# Handmouse_Sch.net
KiCad netlist of a schematic drawn in Altium Designer
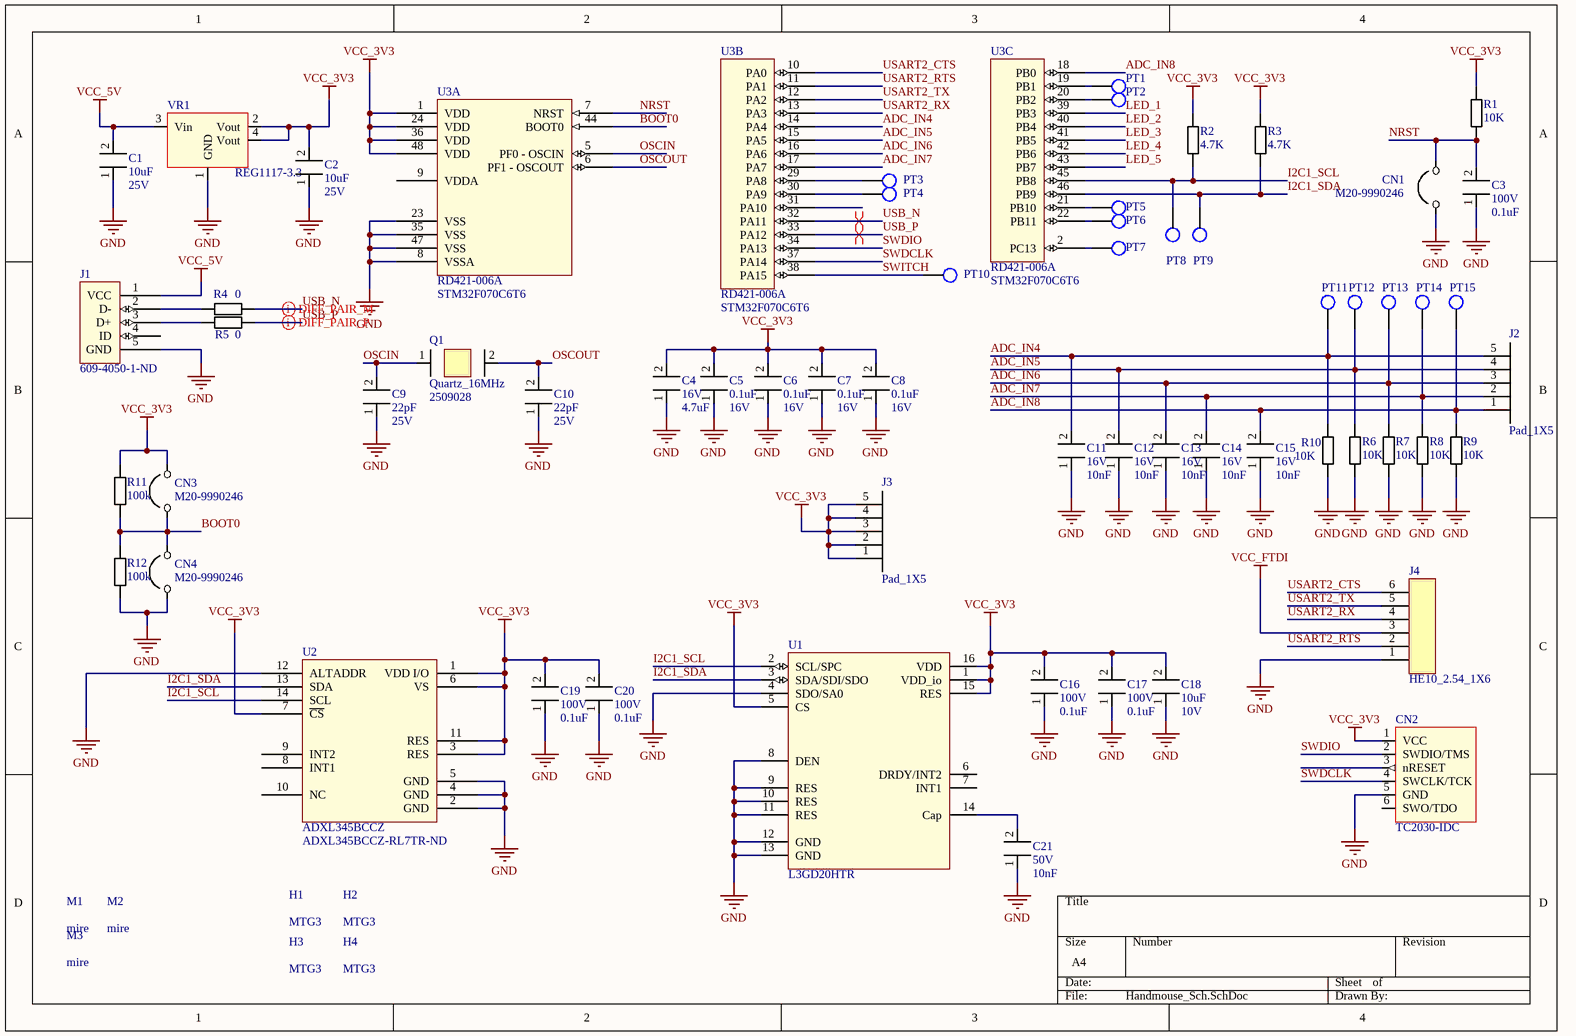
[diagram p0: Handmouse_Sch.SchDoc]

(export (version "E")
  (design (tool "Eeschema 10.0.6"))
  (components
    (comp (ref "C1")
      (value "RD401-040A")
      (footprint "1206")
      (description "CAP CER 1206 10uF 25V X7R 10%")
      (fields
        (field (name "MANUFACTURER") "MURATA")
        (field (name "MANUFACTURER PART NUMBER") "GRM31CR71E106KA12L")
        (field (name "CAPACITÉ") "10uF")
        (field (name "TENSION") "25V")
      )
      (libsource (lib "Condensateur") (part "RD401-040A"))
    )
    (comp (ref "C2")
      (value "RD401-040A")
      (footprint "1206")
      (description "CAP CER 1206 10uF 25V X7R 10%")
      (fields
        (field (name "MANUFACTURER") "MURATA")
        (field (name "MANUFACTURER PART NUMBER") "GRM31CR71E106KA12L")
        (field (name "CAPACITÉ") "10uF")
        (field (name "TENSION") "25V")
      )
      (libsource (lib "Condensateur") (part "RD401-040A"))
    )
    (comp (ref "C3")
      (value "RD401-002A")
      (footprint "0805")
      (description "CAP CER 0805 0.1uF 100V X7R 5%")
      (fields
        (field (name "TENSION") "100V")
        (field (name "CAPACITÉ") "0.1uF")
        (field (name "HAUTEUR DU BOÎTIER") "1.4 mm")
      )
      (libsource (lib "Condensateur") (part "RD401-002A"))
    )
    (comp (ref "C4")
      (value "~")
      (footprint "0805")
      (description "CAP CER 0805 4.7uF 16V X7R 10%")
      (fields
        (field (name "MANUFACTURER") "AVX")
        (field (name "MANUFACTURER PART NUMBER") "0805YC475KAT2A")
        (field (name "VOLTAGE") "16V")
        (field (name "CAPACITÉ") "4.7uF")
      )
      (libsource (lib "Condensateur") (part "RD401-025A"))
    )
    (comp (ref "C5")
      (value "RD401-033A")
      (footprint "0402")
      (description "CAP CER 0402 0.1uF 16V X7R 5%")
      (fields
        (field (name "MANUFACTURER") "KEMET")
        (field (name "MANUFACTURER PART NUMBER") "C0402C104J4RACTU")
        (field (name "CAPACITÉ") "0.1uF")
        (field (name "VOLTAGE") "16V")
      )
      (libsource (lib "Condensateur") (part "RD401-033A"))
    )
    (comp (ref "C6")
      (value "RD401-033A")
      (footprint "0402")
      (description "CAP CER 0402 0.1uF 16V X7R 5%")
      (fields
        (field (name "MANUFACTURER") "KEMET")
        (field (name "MANUFACTURER PART NUMBER") "C0402C104J4RACTU")
        (field (name "CAPACITÉ") "0.1uF")
        (field (name "VOLTAGE") "16V")
      )
      (libsource (lib "Condensateur") (part "RD401-033A"))
    )
    (comp (ref "C7")
      (value "RD401-033A")
      (footprint "0402")
      (description "CAP CER 0402 0.1uF 16V X7R 5%")
      (fields
        (field (name "MANUFACTURER") "KEMET")
        (field (name "MANUFACTURER PART NUMBER") "C0402C104J4RACTU")
        (field (name "CAPACITÉ") "0.1uF")
        (field (name "VOLTAGE") "16V")
      )
      (libsource (lib "Condensateur") (part "RD401-033A"))
    )
    (comp (ref "C8")
      (value "RD401-033A")
      (footprint "0402")
      (description "CAP CER 0402 0.1uF 16V X7R 5%")
      (fields
        (field (name "MANUFACTURER") "KEMET")
        (field (name "MANUFACTURER PART NUMBER") "C0402C104J4RACTU")
        (field (name "CAPACITÉ") "0.1uF")
        (field (name "VOLTAGE") "16V")
      )
      (libsource (lib "Condensateur") (part "RD401-033A"))
    )
    (comp (ref "C9")
      (value "22pF")
      (footprint "0402")
      (description "CAP CER 0402 22pF 25V COG 1%")
      (fields (field (name "VOLTAGE") "25V"))
      (libsource (lib "Condensateur") (part "RD401-009A"))
    )
    (comp (ref "C10")
      (value "22pF")
      (footprint "0402")
      (description "CAP CER 0402 22pF 25V COG 1%")
      (fields (field (name "VOLTAGE") "25V"))
      (libsource (lib "Condensateur") (part "RD401-009A"))
    )
    (comp (ref "C11")
      (value "RD401-008A")
      (footprint "0402")
      (description "CAP CER 0402 10nF 16V X7R 5%")
      (fields (field (name "VOLTAGE") "16V") (field (name "CAPACITÉ") "10nF"))
      (libsource (lib "Condensateur") (part "RD401-008A"))
    )
    (comp (ref "C12")
      (value "RD401-008A")
      (footprint "0402")
      (description "CAP CER 0402 10nF 16V X7R 5%")
      (fields (field (name "VOLTAGE") "16V") (field (name "CAPACITÉ") "10nF"))
      (libsource (lib "Condensateur") (part "RD401-008A"))
    )
    (comp (ref "C13")
      (value "RD401-008A")
      (footprint "0402")
      (description "CAP CER 0402 10nF 16V X7R 5%")
      (fields (field (name "VOLTAGE") "16V") (field (name "CAPACITÉ") "10nF"))
      (libsource (lib "Condensateur") (part "RD401-008A"))
    )
    (comp (ref "C14")
      (value "RD401-008A")
      (footprint "0402")
      (description "CAP CER 0402 10nF 16V X7R 5%")
      (fields (field (name "VOLTAGE") "16V") (field (name "CAPACITÉ") "10nF"))
      (libsource (lib "Condensateur") (part "RD401-008A"))
    )
    (comp (ref "C15")
      (value "RD401-008A")
      (footprint "0402")
      (description "CAP CER 0402 10nF 16V X7R 5%")
      (fields (field (name "VOLTAGE") "16V") (field (name "CAPACITÉ") "10nF"))
      (libsource (lib "Condensateur") (part "RD401-008A"))
    )
    (comp (ref "C16")
      (value "RD401-002A")
      (footprint "0805")
      (description "CAP CER 0805 0.1uF 100V X7R 5%")
      (fields
        (field (name "TENSION") "100V")
        (field (name "CAPACITÉ") "0.1uF")
        (field (name "HAUTEUR DU BOÎTIER") "1.4 mm")
      )
      (libsource (lib "Condensateur") (part "RD401-002A"))
    )
    (comp (ref "C17")
      (value "RD401-002A")
      (footprint "0805")
      (description "CAP CER 0805 0.1uF 100V X7R 5%")
      (fields
        (field (name "TENSION") "100V")
        (field (name "CAPACITÉ") "0.1uF")
        (field (name "HAUTEUR DU BOÎTIER") "1.4 mm")
      )
      (libsource (lib "Condensateur") (part "RD401-002A"))
    )
    (comp (ref "C18")
      (value "RD401-042A")
      (footprint "0805")
      (description "CAP CER 0805 10uF 10V X7R 10%")
      (fields
        (field (name "MANUFACTURER") "MURATA")
        (field (name "MANUFACTURER PART NUMBER") "GRM21BR71A106KE51L")
        (field (name "CAPACITÉ") "10uF")
        (field (name "TENSION") "10V")
      )
      (libsource (lib "Condensateur") (part "RD401-042A"))
    )
    (comp (ref "C19")
      (value "RD401-002A")
      (footprint "0805")
      (description "CAP CER 0805 0.1uF 100V X7R 5%")
      (fields
        (field (name "TENSION") "100V")
        (field (name "CAPACITÉ") "0.1uF")
        (field (name "HAUTEUR DU BOÎTIER") "1.4 mm")
      )
      (libsource (lib "Condensateur") (part "RD401-002A"))
    )
    (comp (ref "C20")
      (value "RD401-002A")
      (footprint "0805")
      (description "CAP CER 0805 0.1uF 100V X7R 5%")
      (fields
        (field (name "TENSION") "100V")
        (field (name "CAPACITÉ") "0.1uF")
        (field (name "HAUTEUR DU BOÎTIER") "1.4 mm")
      )
      (libsource (lib "Condensateur") (part "RD401-002A"))
    )
    (comp (ref "C21")
      (value "RD401-037A")
      (footprint "0402")
      (description "CAP CER 0402 10nF 50V X7R 10%")
      (fields
        (field (name "MANUFACTURER") "KEMET")
        (field (name "MANUFACTURER PART NUMBER") "C0402C103K5RACTU")
        (field (name "VOLTAGE") "50V")
        (field (name "CAPACITE") "10nF")
      )
      (libsource (lib "Condensateur") (part "RD401-037A"))
    )
    (comp (ref "CN1")
      (value "RD408-013A")
      (footprint "PinHead 2*1 M")
      (description "JUMPER")
      (fields (field (name "MANUFACTURER PART NUMBER 1") "M20-9990246"))
      (libsource (lib "Connecteur") (part "RD408-013A"))
    )
    (comp (ref "CN2")
      (value "RD408-022A")
      (footprint "TC2030-IDC-FP")
      (description "CON SWD")
      (fields
        (field (name "MANUFACTURER") "Tag-Connect LLC")
        (field (name "MANUFACTURER PART NUMBER") "TC2030-IDC")
      )
      (libsource (lib "Connecteur") (part "RD408-022A"))
    )
    (comp (ref "CN3")
      (value "RD408-013A")
      (footprint "PinHead 2*1 M")
      (description "JUMPER")
      (fields (field (name "MANUFACTURER PART NUMBER 1") "M20-9990246"))
      (libsource (lib "Connecteur") (part "RD408-013A"))
    )
    (comp (ref "CN4")
      (value "RD408-013A")
      (footprint "PinHead 2*1 M")
      (description "JUMPER")
      (fields (field (name "MANUFACTURER PART NUMBER 1") "M20-9990246"))
      (libsource (lib "Connecteur") (part "RD408-013A"))
    )
    (comp (ref "H1")
      (value "MTG3")
      (footprint "MTG3")
      (description "Mounting hole M3")
      (libsource (lib "Miscellaneous") (part "MTG3"))
    )
    (comp (ref "H2")
      (value "MTG3")
      (footprint "MTG3")
      (description "Mounting hole M3")
      (libsource (lib "Miscellaneous") (part "MTG3"))
    )
    (comp (ref "H3")
      (value "MTG3")
      (footprint "MTG3")
      (description "Mounting hole M3")
      (libsource (lib "Miscellaneous") (part "MTG3"))
    )
    (comp (ref "H4")
      (value "MTG3")
      (footprint "MTG3")
      (description "Mounting hole M3")
      (libsource (lib "Miscellaneous") (part "MTG3"))
    )
    (comp (ref "J1")
      (value "CONN_FCI_10103594-0001LF")
      (description "CONN MICROUSB FCI 10103594-0001LF")
      (fields
        (field (name "MANUFACTURER") "Amphenol FCI")
        (field (name "MANUFACTURER PART NUMBER") "10103594-0001LF")
        (field (name "SUPPLIER PART NUMBER 1") "609-4050-1-ND")
      )
      (libsource (lib "Schlib1") (part "CONN_FCI_10103594-0001LF"))
    )
    (comp (ref "J2") (value "Pad_1X5") (libsource (lib "Schlib1") (part "Pad_1X5")))
    (comp (ref "J3") (value "Pad_1X5") (libsource (lib "Schlib1") (part "Pad_1X5")))
    (comp (ref "J4") (value "HE10_2.54_1X6") (libsource (lib "Schlib1") (part "HE10_2.54_1X6")))
    (comp (ref "M1")
      (value "mire")
      (footprint "Miscellaneous:Mire")
      (libsource (lib "Miscellaneous") (part "mire"))
    )
    (comp (ref "M2")
      (value "mire")
      (footprint "Miscellaneous:Mire")
      (libsource (lib "Miscellaneous") (part "mire"))
    )
    (comp (ref "M3")
      (value "mire")
      (footprint "Miscellaneous:Mire")
      (libsource (lib "Miscellaneous") (part "mire"))
    )
    (comp (ref "PT1")
      (value "PT 0.8mm")
      (description "Point de test pastille 0.8mm")
      (libsource (lib "Schlib1") (part "PT 0.8mm"))
    )
    (comp (ref "PT2")
      (value "PT 0.8mm")
      (description "Point de test pastille 0.8mm")
      (libsource (lib "Schlib1") (part "PT 0.8mm"))
    )
    (comp (ref "PT3")
      (value "PT 0.8mm")
      (description "Point de test pastille 0.8mm")
      (libsource (lib "Schlib1") (part "PT 0.8mm"))
    )
    (comp (ref "PT4")
      (value "PT 0.8mm")
      (description "Point de test pastille 0.8mm")
      (libsource (lib "Schlib1") (part "PT 0.8mm"))
    )
    (comp (ref "PT5")
      (value "PT 0.8mm")
      (description "Point de test pastille 0.8mm")
      (libsource (lib "Schlib1") (part "PT 0.8mm"))
    )
    (comp (ref "PT6")
      (value "PT 0.8mm")
      (description "Point de test pastille 0.8mm")
      (libsource (lib "Schlib1") (part "PT 0.8mm"))
    )
    (comp (ref "PT7")
      (value "PT 0.8mm")
      (description "Point de test pastille 0.8mm")
      (libsource (lib "Schlib1") (part "PT 0.8mm"))
    )
    (comp (ref "PT8")
      (value "PT 0.8mm")
      (description "Point de test pastille 0.8mm")
      (libsource (lib "Schlib1") (part "PT 0.8mm"))
    )
    (comp (ref "PT9")
      (value "PT 0.8mm")
      (description "Point de test pastille 0.8mm")
      (libsource (lib "Schlib1") (part "PT 0.8mm"))
    )
    (comp (ref "PT10")
      (value "PT 0.8mm")
      (description "Point de test pastille 0.8mm")
      (libsource (lib "Schlib1") (part "PT 0.8mm"))
    )
    (comp (ref "PT11")
      (value "PT 0.8mm")
      (description "Point de test pastille 0.8mm")
      (libsource (lib "Schlib1") (part "PT 0.8mm"))
    )
    (comp (ref "PT12")
      (value "PT 0.8mm")
      (description "Point de test pastille 0.8mm")
      (libsource (lib "Schlib1") (part "PT 0.8mm"))
    )
    (comp (ref "PT13")
      (value "PT 0.8mm")
      (description "Point de test pastille 0.8mm")
      (libsource (lib "Schlib1") (part "PT 0.8mm"))
    )
    (comp (ref "PT14")
      (value "PT 0.8mm")
      (description "Point de test pastille 0.8mm")
      (libsource (lib "Schlib1") (part "PT 0.8mm"))
    )
    (comp (ref "PT15")
      (value "PT 0.8mm")
      (description "Point de test pastille 0.8mm")
      (libsource (lib "Schlib1") (part "PT 0.8mm"))
    )
    (comp (ref "Q1")
      (value "Quartz_16MHz")
      (description "Quartz 16MHz")
      (fields
        (field (name "MANUFACTURER") "RALTRON")
        (field (name "MANUFACTURER PART NUMBER") "AS-16.000-18-SMD")
        (field (name "SUPPLIER PART NUMBER 1") "2509028")
      )
      (libsource (lib "Schlib1") (part "Quartz_16MHz"))
    )
    (comp (ref "R1")
      (value "RD403-054A")
      (footprint "0603")
      (description "RES 0603 10K 1% 0.1W")
      (fields
        (field (name "MANUFACTURER") "VISHAY DRALORIC")
        (field (name "MANUFACTURER PART NUMBER") "CRCW060310K0FKEA")
        (field (name "RESISTANCE") "10K")
      )
      (libsource (lib "Resistance") (part "RD403-054A"))
    )
    (comp (ref "R2")
      (value "RD403-046A")
      (footprint "0603")
      (description "RES 0603 4.7K 1% 0.1W")
      (fields
        (field (name "MANUFACTURER") "Vishay Dale")
        (field (name "MANUFACTURER PART NUMBER") "CRCW06034K70FKEA")
        (field (name "RÉSISTANCE (OHMS)") "4.7K")
        (field (name "HAUTEUR") "0,020 po (0,50 mm)")
      )
      (libsource (lib "Resistance") (part "RD403-046A"))
    )
    (comp (ref "R3")
      (value "RD403-046A")
      (footprint "0603")
      (description "RES 0603 4.7K 1% 0.1W")
      (fields
        (field (name "MANUFACTURER") "Vishay Dale")
        (field (name "MANUFACTURER PART NUMBER") "CRCW06034K70FKEA")
        (field (name "RÉSISTANCE (OHMS)") "4.7K")
        (field (name "HAUTEUR") "0,020 po (0,50 mm)")
      )
      (libsource (lib "Resistance") (part "RD403-046A"))
    )
    (comp (ref "R4")
      (value "RD403-044A")
      (footprint "0603")
      (description "RES 0603 0 1% 0.1W")
      (fields
        (field (name "MANUFACTURER") "VISHAY DRALORIC")
        (field (name "MANUFACTURER PART NUMBER") "CRCW06030000Z0EA")
        (field (name "RÉSISTANCE") "0")
      )
      (libsource (lib "Resistance") (part "RD403-044A"))
    )
    (comp (ref "R5")
      (value "RD403-044A")
      (footprint "0603")
      (description "RES 0603 0 1% 0.1W")
      (fields
        (field (name "MANUFACTURER") "VISHAY DRALORIC")
        (field (name "MANUFACTURER PART NUMBER") "CRCW06030000Z0EA")
        (field (name "RÉSISTANCE") "0")
      )
      (libsource (lib "Resistance") (part "RD403-044A"))
    )
    (comp (ref "R6")
      (value "RD403-054A")
      (footprint "0603")
      (description "RES 0603 10K 1% 0.1W")
      (fields
        (field (name "MANUFACTURER") "VISHAY DRALORIC")
        (field (name "MANUFACTURER PART NUMBER") "CRCW060310K0FKEA")
        (field (name "RESISTANCE") "10K")
      )
      (libsource (lib "Resistance") (part "RD403-054A"))
    )
    (comp (ref "R7")
      (value "RD403-054A")
      (footprint "0603")
      (description "RES 0603 10K 1% 0.1W")
      (fields
        (field (name "MANUFACTURER") "VISHAY DRALORIC")
        (field (name "MANUFACTURER PART NUMBER") "CRCW060310K0FKEA")
        (field (name "RESISTANCE") "10K")
      )
      (libsource (lib "Resistance") (part "RD403-054A"))
    )
    (comp (ref "R8")
      (value "RD403-054A")
      (footprint "0603")
      (description "RES 0603 10K 1% 0.1W")
      (fields
        (field (name "MANUFACTURER") "VISHAY DRALORIC")
        (field (name "MANUFACTURER PART NUMBER") "CRCW060310K0FKEA")
        (field (name "RESISTANCE") "10K")
      )
      (libsource (lib "Resistance") (part "RD403-054A"))
    )
    (comp (ref "R9")
      (value "RD403-054A")
      (footprint "0603")
      (description "RES 0603 10K 1% 0.1W")
      (fields
        (field (name "MANUFACTURER") "VISHAY DRALORIC")
        (field (name "MANUFACTURER PART NUMBER") "CRCW060310K0FKEA")
        (field (name "RESISTANCE") "10K")
      )
      (libsource (lib "Resistance") (part "RD403-054A"))
    )
    (comp (ref "R10")
      (value "RD403-054A")
      (footprint "0603")
      (description "RES 0603 10K 1% 0.1W")
      (fields
        (field (name "MANUFACTURER") "VISHAY DRALORIC")
        (field (name "MANUFACTURER PART NUMBER") "CRCW060310K0FKEA")
        (field (name "RESISTANCE") "10K")
      )
      (libsource (lib "Resistance") (part "RD403-054A"))
    )
    (comp (ref "R11")
      (value "100k")
      (footprint "0402")
      (description "RES 0402 100k 1% 0.063W")
      (libsource (lib "Resistance") (part "RD403-007A"))
    )
    (comp (ref "R12")
      (value "100k")
      (footprint "0402")
      (description "RES 0402 100k 1% 0.063W")
      (libsource (lib "Resistance") (part "RD403-007A"))
    )
    (comp (ref "U1")
      (value "RD498-005A")
      (footprint "LGA_50P_300X300_16")
      (description "Gyroscopes MEMS motion sensor 3axis digital output")
      (fields (field (name "MANUFACTURER PART NUMBER 1") "L3GD20HTR") (field (name "HAUTEUR") "1 mm"))
      (libsource (lib "Miscellaneous") (part "RD498-005A"))
    )
    (comp (ref "U2")
      (value "ADXL345BCCZ")
      (fields
        (field (name "MANUFACTURER") "Analog Devices Inc.")
        (field (name "MANUFACTURER PART NUMBER") "ADXL345BCCZ-RL7")
        (field (name "SUPPLIER PART NUMBER 1") "ADXL345BCCZ-RL7TR-ND")
      )
      (libsource (lib "Schlib1") (part "ADXL345BCCZ"))
    )
    (comp (ref "U3")
      (value "RD421-006A")
      (description "STM32F070C6T6")
      (fields
        (field (name "MANUFACTURER") "STMICROELECTRONICS")
        (field (name "MANUFACTURER PART NUMBER") "STM32F070C6T6")
      )
      (libsource (lib "SOC") (part "RD421-006A"))
    )
    (comp (ref "VR1")
      (value "RD426-001A")
      (footprint "R-PDSO- G4")
      (description "REG LIN SOT223 3V3 1A 3.8V 15V")
      (fields (field (name "MANUFACTURER PART NUMBER 1") "REG1117-3.3"))
      (libsource (lib "Lineaire") (part "RD426-001A"))
    )
  )
  (nets
    (net (code "1") (name "/ADC_IN4") (class "Default")
      (node (ref "C11") (pin "2") (pinfunction "2_2") (pintype "passive"))
      (node (ref "J2") (pin "5") (pinfunction "5_5") (pintype "passive"))
      (node (ref "PT11") (pin "1") (pinfunction "1_1") (pintype "passive"))
      (node (ref "R10") (pin "2") (pinfunction "4_2") (pintype "passive"))
      (node (ref "U3") (pin "14") (pinfunction "PA4_14") (pintype "bidirectional"))
    )
    (net (code "2") (name "/ADC_IN5") (class "Default")
      (node (ref "C12") (pin "2") (pinfunction "2_2") (pintype "passive"))
      (node (ref "J2") (pin "4") (pinfunction "4_4") (pintype "passive"))
      (node (ref "PT12") (pin "1") (pinfunction "1_1") (pintype "passive"))
      (node (ref "R6") (pin "2") (pinfunction "4_2") (pintype "passive"))
      (node (ref "U3") (pin "15") (pinfunction "PA5_15") (pintype "bidirectional"))
    )
    (net (code "3") (name "/ADC_IN6") (class "Default")
      (node (ref "C13") (pin "2") (pinfunction "2_2") (pintype "passive"))
      (node (ref "J2") (pin "3") (pinfunction "3_3") (pintype "passive"))
      (node (ref "PT13") (pin "1") (pinfunction "1_1") (pintype "passive"))
      (node (ref "R7") (pin "2") (pinfunction "4_2") (pintype "passive"))
      (node (ref "U3") (pin "16") (pinfunction "PA6_16") (pintype "bidirectional"))
    )
    (net (code "4") (name "/ADC_IN7") (class "Default")
      (node (ref "C14") (pin "2") (pinfunction "2_2") (pintype "passive"))
      (node (ref "J2") (pin "2") (pinfunction "2_2") (pintype "passive"))
      (node (ref "PT14") (pin "1") (pinfunction "1_1") (pintype "passive"))
      (node (ref "R8") (pin "2") (pinfunction "4_2") (pintype "passive"))
      (node (ref "U3") (pin "17") (pinfunction "PA7_17") (pintype "bidirectional"))
    )
    (net (code "5") (name "/ADC_IN8") (class "Default")
      (node (ref "C15") (pin "2") (pinfunction "2_2") (pintype "passive"))
      (node (ref "J2") (pin "1") (pinfunction "1_1") (pintype "passive"))
      (node (ref "PT15") (pin "1") (pinfunction "1_1") (pintype "passive"))
      (node (ref "R9") (pin "2") (pinfunction "4_2") (pintype "passive"))
      (node (ref "U3") (pin "18") (pinfunction "PB0_18") (pintype "bidirectional"))
    )
    (net (code "6") (name "/BOOT0") (class "Default")
      (node (ref "CN3") (pin "1") (pinfunction "1_1") (pintype "power_in"))
      (node (ref "CN4") (pin "2") (pinfunction "2_2") (pintype "power_in"))
      (node (ref "R11") (pin "1") (pinfunction "3_1") (pintype "passive"))
      (node (ref "R12") (pin "2") (pinfunction "4_2") (pintype "passive"))
      (node (ref "U3") (pin "44") (pinfunction "BOOT0_44") (pintype "input"))
    )
    (net (code "7") (name "/I2C1_SCL") (class "Default")
      (node (ref "PT8") (pin "1") (pinfunction "1_1") (pintype "passive"))
      (node (ref "R2") (pin "1") (pinfunction "3_1") (pintype "passive"))
      (node (ref "U1") (pin "2") (pinfunction "SCL/SPC_2") (pintype "bidirectional"))
      (node (ref "U2") (pin "14") (pinfunction "SCL_14") (pintype "passive"))
      (node (ref "U3") (pin "45") (pinfunction "PB8_45") (pintype "bidirectional"))
    )
    (net (code "8") (name "/I2C1_SDA") (class "Default")
      (node (ref "PT9") (pin "1") (pinfunction "1_1") (pintype "passive"))
      (node (ref "R3") (pin "1") (pinfunction "3_1") (pintype "passive"))
      (node (ref "U1") (pin "3") (pinfunction "SDA/SDI/SDO_3") (pintype "bidirectional"))
      (node (ref "U2") (pin "13") (pinfunction "SDA_13") (pintype "passive"))
      (node (ref "U3") (pin "46") (pinfunction "PB9_46") (pintype "bidirectional"))
    )
    (net (code "9") (name "/LED_1") (class "Default")
      (node (ref "U3") (pin "39") (pinfunction "PB3_39") (pintype "bidirectional"))
    )
    (net (code "10") (name "/LED_2") (class "Default")
      (node (ref "U3") (pin "40") (pinfunction "PB4_40") (pintype "bidirectional"))
    )
    (net (code "11") (name "/LED_3") (class "Default")
      (node (ref "U3") (pin "41") (pinfunction "PB5_41") (pintype "bidirectional"))
    )
    (net (code "12") (name "/LED_4") (class "Default")
      (node (ref "U3") (pin "42") (pinfunction "PB6_42") (pintype "bidirectional"))
    )
    (net (code "13") (name "/LED_5") (class "Default")
      (node (ref "U3") (pin "43") (pinfunction "PB7_43") (pintype "bidirectional"))
    )
    (net (code "14") (name "/NRST") (class "Default")
      (node (ref "C3") (pin "2") (pinfunction "2_2") (pintype "passive"))
      (node (ref "CN1") (pin "2") (pinfunction "2_2") (pintype "power_in"))
      (node (ref "R1") (pin "1") (pinfunction "3_1") (pintype "passive"))
      (node (ref "U3") (pin "7") (pinfunction "NRST_7") (pintype "input"))
    )
    (net (code "15") (name "/OSCIN") (class "Default")
      (node (ref "C9") (pin "2") (pinfunction "2_2") (pintype "passive"))
      (node (ref "Q1") (pin "1") (pinfunction "1_1") (pintype "passive"))
      (node (ref "U3") (pin "5") (pinfunction "PF0_-_OSCIN_5") (pintype "bidirectional"))
    )
    (net (code "16") (name "/OSCOUT") (class "Default")
      (node (ref "C10") (pin "2") (pinfunction "2_2") (pintype "passive"))
      (node (ref "Q1") (pin "2") (pinfunction "2_2") (pintype "passive"))
      (node (ref "U3") (pin "6") (pinfunction "PF1_-_OSCOUT_6") (pintype "bidirectional"))
    )
    (net (code "17") (name "/SWDCLK") (class "Default")
      (node (ref "CN2") (pin "4") (pinfunction "SWCLK/TCK_4") (pintype "bidirectional"))
      (node (ref "U3") (pin "37") (pinfunction "PA14_37") (pintype "bidirectional"))
    )
    (net (code "18") (name "/SWDIO") (class "Default")
      (node (ref "CN2") (pin "2") (pinfunction "SWDIO/TMS_2") (pintype "bidirectional"))
      (node (ref "U3") (pin "34") (pinfunction "PA13_34") (pintype "bidirectional"))
    )
    (net (code "19") (name "/SWITCH") (class "Default")
      (node (ref "PT10") (pin "1") (pinfunction "1_1") (pintype "passive"))
      (node (ref "U3") (pin "38") (pinfunction "PA15_38") (pintype "bidirectional"))
    )
    (net (code "20") (name "/USART2_CTS") (class "Default")
      (node (ref "J4") (pin "6") (pinfunction "6_6") (pintype "passive"))
      (node (ref "U3") (pin "10") (pinfunction "PA0_10") (pintype "bidirectional"))
    )
    (net (code "21") (name "/USART2_RTS") (class "Default")
      (node (ref "J4") (pin "2") (pinfunction "2_2") (pintype "passive"))
      (node (ref "U3") (pin "11") (pinfunction "PA1_11") (pintype "bidirectional"))
    )
    (net (code "22") (name "/USART2_RX") (class "Default")
      (node (ref "J4") (pin "4") (pinfunction "4_4") (pintype "passive"))
      (node (ref "U3") (pin "13") (pinfunction "PA3_13") (pintype "bidirectional"))
    )
    (net (code "23") (name "/USART2_TX") (class "Default")
      (node (ref "J4") (pin "5") (pinfunction "5_5") (pintype "passive"))
      (node (ref "U3") (pin "12") (pinfunction "PA2_12") (pintype "bidirectional"))
    )
    (net (code "24") (name "/USB_N") (class "Default")
      (node (ref "R4") (pin "2") (pinfunction "4_2") (pintype "passive"))
      (node (ref "U3") (pin "32") (pinfunction "PA11_32") (pintype "bidirectional"))
    )
    (net (code "25") (name "/USB_P") (class "Default")
      (node (ref "R5") (pin "2") (pinfunction "4_2") (pintype "passive"))
      (node (ref "U3") (pin "33") (pinfunction "PA12_33") (pintype "bidirectional"))
    )
    (net (code "26") (name "GND") (class "Default")
      (node (ref "C1") (pin "1") (pinfunction "1_1") (pintype "passive"))
      (node (ref "C10") (pin "1") (pinfunction "1_1") (pintype "passive"))
      (node (ref "C11") (pin "1") (pinfunction "1_1") (pintype "passive"))
      (node (ref "C12") (pin "1") (pinfunction "1_1") (pintype "passive"))
      (node (ref "C13") (pin "1") (pinfunction "1_1") (pintype "passive"))
      (node (ref "C14") (pin "1") (pinfunction "1_1") (pintype "passive"))
      (node (ref "C15") (pin "1") (pinfunction "1_1") (pintype "passive"))
      (node (ref "C16") (pin "1") (pinfunction "1_1") (pintype "passive"))
      (node (ref "C17") (pin "1") (pinfunction "1_1") (pintype "passive"))
      (node (ref "C18") (pin "1") (pinfunction "1_1") (pintype "passive"))
      (node (ref "C19") (pin "1") (pinfunction "1_1") (pintype "passive"))
      (node (ref "C2") (pin "1") (pinfunction "1_1") (pintype "passive"))
      (node (ref "C20") (pin "1") (pinfunction "1_1") (pintype "passive"))
      (node (ref "C21") (pin "1") (pinfunction "1_1") (pintype "passive"))
      (node (ref "C3") (pin "1") (pinfunction "1_1") (pintype "passive"))
      (node (ref "C4") (pin "1") (pinfunction "1_1") (pintype "passive"))
      (node (ref "C5") (pin "1") (pinfunction "1_1") (pintype "passive"))
      (node (ref "C6") (pin "1") (pinfunction "1_1") (pintype "passive"))
      (node (ref "C7") (pin "1") (pinfunction "1_1") (pintype "passive"))
      (node (ref "C8") (pin "1") (pinfunction "1_1") (pintype "passive"))
      (node (ref "C9") (pin "1") (pinfunction "1_1") (pintype "passive"))
      (node (ref "CN1") (pin "1") (pinfunction "1_1") (pintype "power_in"))
      (node (ref "CN2") (pin "5") (pinfunction "GND_5") (pintype "power_in"))
      (node (ref "CN4") (pin "1") (pinfunction "1_1") (pintype "power_in"))
      (node (ref "J1") (pin "5") (pinfunction "GND_5") (pintype "power_in"))
      (node (ref "J4") (pin "1") (pinfunction "1_1") (pintype "passive"))
      (node (ref "R10") (pin "1") (pinfunction "3_1") (pintype "passive"))
      (node (ref "R12") (pin "1") (pinfunction "3_1") (pintype "passive"))
      (node (ref "R6") (pin "1") (pinfunction "3_1") (pintype "passive"))
      (node (ref "R7") (pin "1") (pinfunction "3_1") (pintype "passive"))
      (node (ref "R8") (pin "1") (pinfunction "3_1") (pintype "passive"))
      (node (ref "R9") (pin "1") (pinfunction "3_1") (pintype "passive"))
      (node (ref "U1") (pin "10") (pinfunction "RES_10") (pintype "passive"))
      (node (ref "U1") (pin "11") (pinfunction "RES_11") (pintype "passive"))
      (node (ref "U1") (pin "12") (pinfunction "GND_12") (pintype "power_in"))
      (node (ref "U1") (pin "13") (pinfunction "GND_13") (pintype "power_in"))
      (node (ref "U1") (pin "4") (pinfunction "SDO/SA0_4") (pintype "passive"))
      (node (ref "U1") (pin "8") (pinfunction "DEN_8") (pintype "passive"))
      (node (ref "U1") (pin "9") (pinfunction "RES_9") (pintype "passive"))
      (node (ref "U2") (pin "12") (pinfunction "ALTADDR_12") (pintype "passive"))
      (node (ref "U2") (pin "2") (pinfunction "GND_2") (pintype "power_in"))
      (node (ref "U2") (pin "4") (pinfunction "GND_4") (pintype "power_in"))
      (node (ref "U2") (pin "5") (pinfunction "GND_5") (pintype "power_in"))
      (node (ref "U3") (pin "23") (pinfunction "VSS_23") (pintype "power_in"))
      (node (ref "U3") (pin "35") (pinfunction "VSS_35") (pintype "power_in"))
      (node (ref "U3") (pin "47") (pinfunction "VSS_47") (pintype "power_in"))
      (node (ref "U3") (pin "8") (pinfunction "VSSA_8") (pintype "power_in"))
      (node (ref "VR1") (pin "1") (pinfunction "GND_1") (pintype "power_in"))
    )
    (net (code "27") (name "Net-(J1-D+)") (class "Default")
      (node (ref "J1") (pin "3") (pinfunction "D+_3") (pintype "bidirectional"))
      (node (ref "R5") (pin "1") (pinfunction "3_1") (pintype "passive"))
    )
    (net (code "28") (name "Net-(J1-D-)") (class "Default")
      (node (ref "J1") (pin "2") (pinfunction "D-_2") (pintype "bidirectional"))
      (node (ref "R4") (pin "1") (pinfunction "3_1") (pintype "passive"))
    )
    (net (code "29") (name "Net-(U1-Cap)") (class "Default")
      (node (ref "C21") (pin "2") (pinfunction "2_2") (pintype "passive"))
      (node (ref "U1") (pin "14") (pinfunction "Cap_14") (pintype "passive"))
    )
    (net (code "30") (name "Net-(U3B-PA8)") (class "Default")
      (node (ref "PT3") (pin "1") (pinfunction "1_1") (pintype "passive"))
      (node (ref "U3") (pin "29") (pinfunction "PA8_29") (pintype "bidirectional"))
    )
    (net (code "31") (name "Net-(U3B-PA9)") (class "Default")
      (node (ref "PT4") (pin "1") (pinfunction "1_1") (pintype "passive"))
      (node (ref "U3") (pin "30") (pinfunction "PA9_30") (pintype "bidirectional"))
    )
    (net (code "32") (name "Net-(U3C-PB1)") (class "Default")
      (node (ref "PT1") (pin "1") (pinfunction "1_1") (pintype "passive"))
      (node (ref "U3") (pin "19") (pinfunction "PB1_19") (pintype "bidirectional"))
    )
    (net (code "33") (name "Net-(U3C-PB2)") (class "Default")
      (node (ref "PT2") (pin "1") (pinfunction "1_1") (pintype "passive"))
      (node (ref "U3") (pin "20") (pinfunction "PB2_20") (pintype "bidirectional"))
    )
    (net (code "34") (name "Net-(U3C-PB10)") (class "Default")
      (node (ref "PT5") (pin "1") (pinfunction "1_1") (pintype "passive"))
      (node (ref "U3") (pin "21") (pinfunction "PB10_21") (pintype "bidirectional"))
    )
    (net (code "35") (name "Net-(U3C-PB11)") (class "Default")
      (node (ref "PT6") (pin "1") (pinfunction "1_1") (pintype "passive"))
      (node (ref "U3") (pin "22") (pinfunction "PB11_22") (pintype "bidirectional"))
    )
    (net (code "36") (name "Net-(U3C-PC13)") (class "Default")
      (node (ref "PT7") (pin "1") (pinfunction "1_1") (pintype "passive"))
      (node (ref "U3") (pin "2") (pinfunction "PC13_2") (pintype "bidirectional"))
    )
    (net (code "37") (name "VCC_3V3") (class "Default")
      (node (ref "C16") (pin "2") (pinfunction "2_2") (pintype "passive"))
      (node (ref "C17") (pin "2") (pinfunction "2_2") (pintype "passive"))
      (node (ref "C18") (pin "2") (pinfunction "2_2") (pintype "passive"))
      (node (ref "C19") (pin "2") (pinfunction "2_2") (pintype "passive"))
      (node (ref "C2") (pin "2") (pinfunction "2_2") (pintype "passive"))
      (node (ref "C20") (pin "2") (pinfunction "2_2") (pintype "passive"))
      (node (ref "C4") (pin "2") (pinfunction "2_2") (pintype "passive"))
      (node (ref "C5") (pin "2") (pinfunction "2_2") (pintype "passive"))
      (node (ref "C6") (pin "2") (pinfunction "2_2") (pintype "passive"))
      (node (ref "C7") (pin "2") (pinfunction "2_2") (pintype "passive"))
      (node (ref "C8") (pin "2") (pinfunction "2_2") (pintype "passive"))
      (node (ref "CN2") (pin "1") (pinfunction "VCC_1") (pintype "power_in"))
      (node (ref "CN3") (pin "2") (pinfunction "2_2") (pintype "power_in"))
      (node (ref "J3") (pin "1") (pinfunction "1_1") (pintype "passive"))
      (node (ref "J3") (pin "2") (pinfunction "2_2") (pintype "passive"))
      (node (ref "J3") (pin "3") (pinfunction "3_3") (pintype "passive"))
      (node (ref "J3") (pin "4") (pinfunction "4_4") (pintype "passive"))
      (node (ref "J3") (pin "5") (pinfunction "5_5") (pintype "passive"))
      (node (ref "R1") (pin "2") (pinfunction "4_2") (pintype "passive"))
      (node (ref "R11") (pin "2") (pinfunction "4_2") (pintype "passive"))
      (node (ref "R2") (pin "2") (pinfunction "4_2") (pintype "passive"))
      (node (ref "R3") (pin "2") (pinfunction "4_2") (pintype "passive"))
      (node (ref "U1") (pin "1") (pinfunction "VDD_io_1") (pintype "power_in"))
      (node (ref "U1") (pin "15") (pinfunction "RES_15") (pintype "passive"))
      (node (ref "U1") (pin "16") (pinfunction "VDD_16") (pintype "power_in"))
      (node (ref "U1") (pin "5") (pinfunction "CS_5") (pintype "passive"))
      (node (ref "U2") (pin "1") (pinfunction "VDD_I/O_1") (pintype "power_in"))
      (node (ref "U2") (pin "11") (pinfunction "RES_11") (pintype "passive"))
      (node (ref "U2") (pin "3") (pinfunction "RES_3") (pintype "power_in"))
      (node (ref "U2") (pin "6") (pinfunction "VS_6") (pintype "power_in"))
      (node (ref "U2") (pin "7") (pinfunction "~{CS}_7") (pintype "power_in"))
      (node (ref "U3") (pin "1") (pinfunction "VDD_1") (pintype "passive"))
      (node (ref "U3") (pin "24") (pinfunction "VDD_24") (pintype "power_in"))
      (node (ref "U3") (pin "36") (pinfunction "VDD_36") (pintype "power_in"))
      (node (ref "U3") (pin "48") (pinfunction "VDD_48") (pintype "power_in"))
      (node (ref "VR1") (pin "2") (pinfunction "Vout_2") (pintype "power_in"))
      (node (ref "VR1") (pin "4") (pinfunction "Vout_4") (pintype "power_in"))
    )
    (net (code "38") (name "VCC_5V") (class "Default")
      (node (ref "C1") (pin "2") (pinfunction "2_2") (pintype "passive"))
      (node (ref "J1") (pin "1") (pinfunction "VCC_1") (pintype "power_in"))
      (node (ref "VR1") (pin "3") (pinfunction "Vin_3") (pintype "power_in"))
    )
    (net (code "39") (name "VCC_FTDI") (class "Default")
      (node (ref "J4") (pin "3") (pinfunction "3_3") (pintype "passive"))
    )
    (net (code "40") (name "unconnected-(CN2-SWO{slash}TDO-Pad6)") (class "Default")
      (node (ref "CN2") (pin "6") (pinfunction "SWO/TDO_6") (pintype "bidirectional"))
    )
    (net (code "41") (name "unconnected-(CN2-nRESET-Pad3)") (class "Default")
      (node (ref "CN2") (pin "3") (pinfunction "nRESET_3") (pintype "output"))
    )
    (net (code "42") (name "unconnected-(J1-ID-Pad4)") (class "Default")
      (node (ref "J1") (pin "4") (pinfunction "ID_4") (pintype "bidirectional"))
    )
    (net (code "43") (name "unconnected-(U1-DRDY{slash}INT2-Pad6)") (class "Default")
      (node (ref "U1") (pin "6") (pinfunction "DRDY/INT2_6") (pintype "passive"))
    )
    (net (code "44") (name "unconnected-(U1-INT1-Pad7)") (class "Default")
      (node (ref "U1") (pin "7") (pinfunction "INT1_7") (pintype "passive"))
    )
    (net (code "45") (name "unconnected-(U2-INT1-Pad8)") (class "Default")
      (node (ref "U2") (pin "8") (pinfunction "INT1_8") (pintype "power_in"))
    )
    (net (code "46") (name "unconnected-(U2-INT2-Pad9)") (class "Default")
      (node (ref "U2") (pin "9") (pinfunction "INT2_9") (pintype "power_in"))
    )
    (net (code "47") (name "unconnected-(U2-NC-Pad10)") (class "Default")
      (node (ref "U2") (pin "10") (pinfunction "NC_10") (pintype "passive"))
    )
    (net (code "48") (name "unconnected-(U3A-VDDA-Pad9)") (class "Default")
      (node (ref "U3") (pin "9") (pinfunction "VDDA_9") (pintype "power_in"))
    )
    (net (code "49") (name "unconnected-(U3B-PA10-Pad31)") (class "Default")
      (node (ref "U3") (pin "31") (pinfunction "PA10_31") (pintype "bidirectional"))
    )
  )
)
